# 3xA4B_rev2.net
KiCad netlist of a schematic drawn in EAGLE
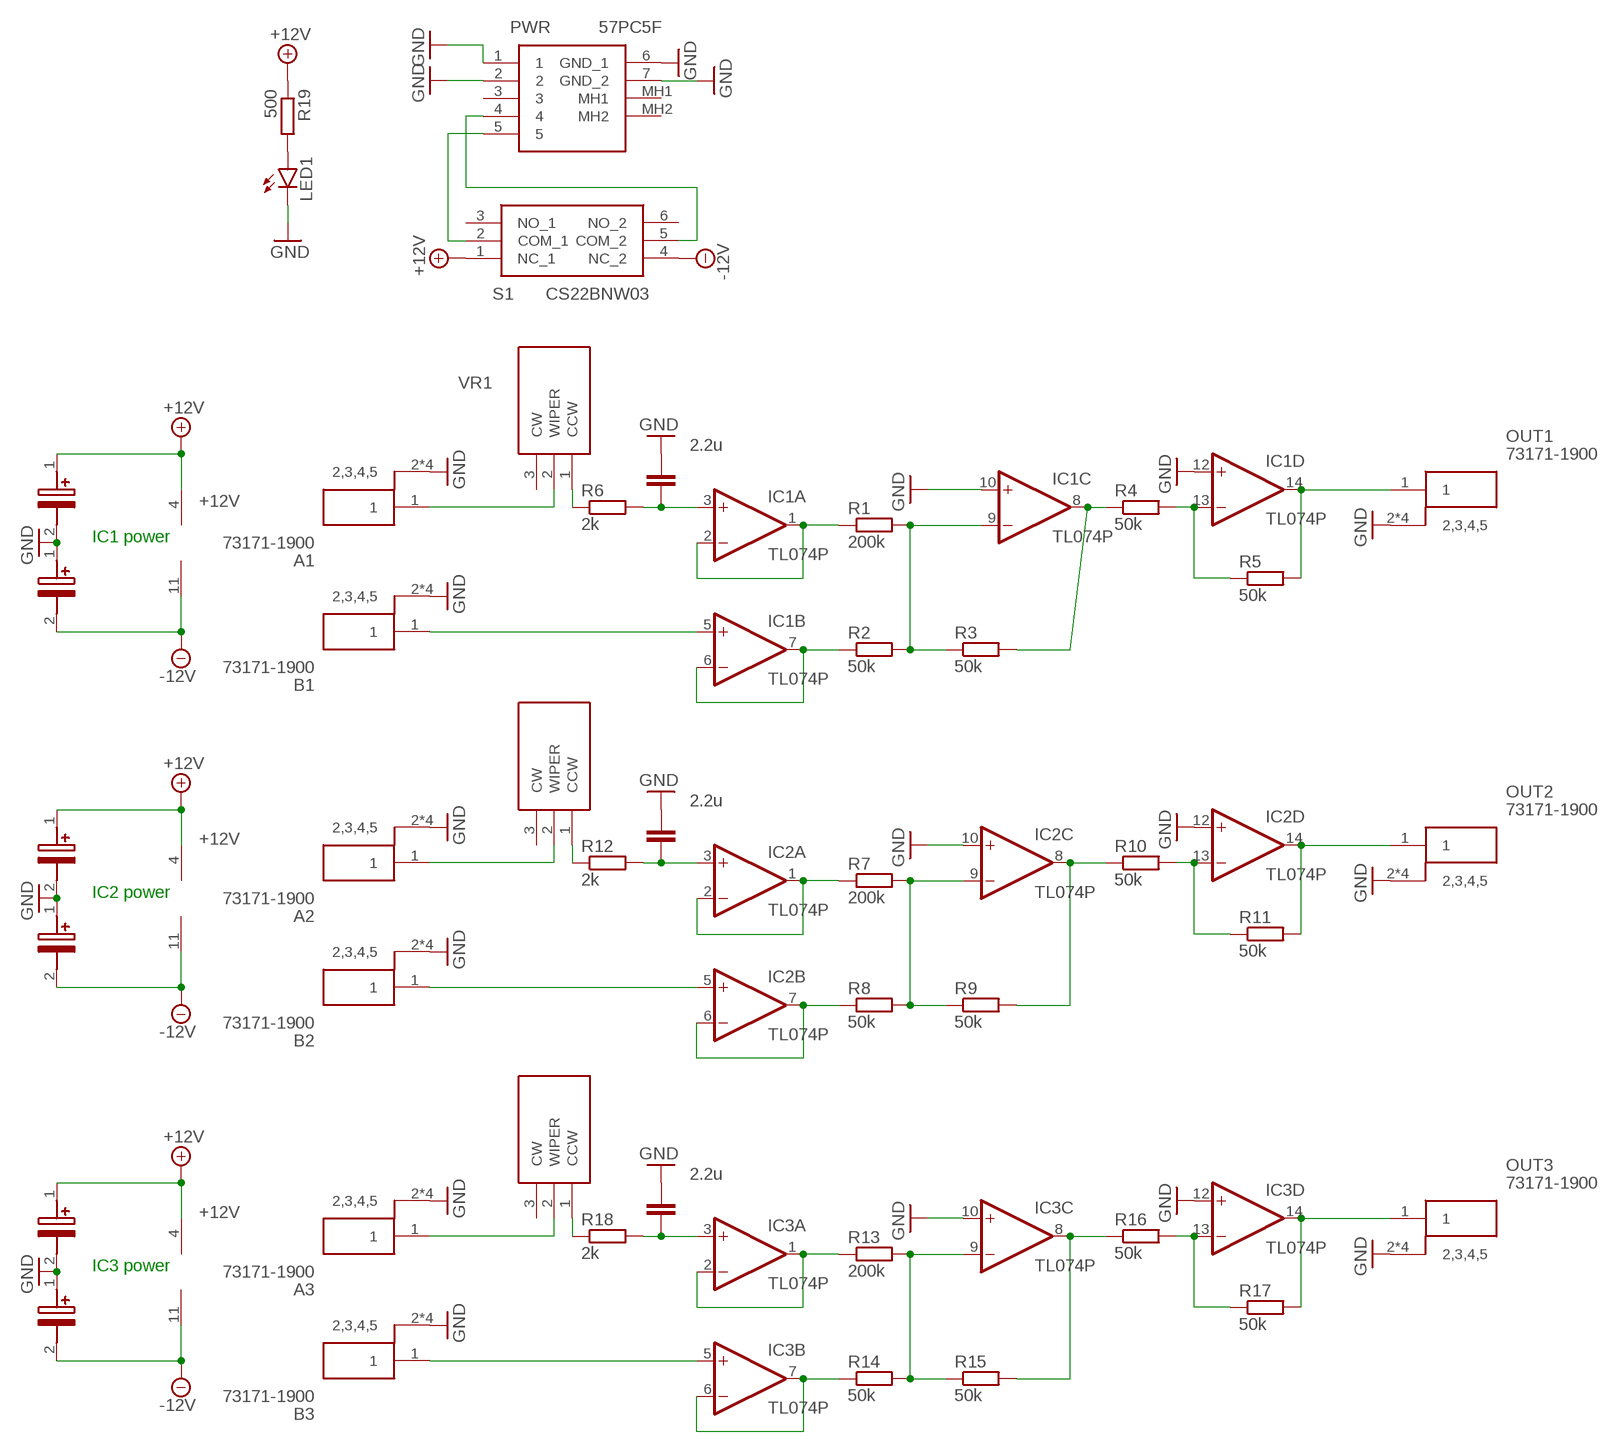
[diagram p0: schematic, sheet 1]

(export (version "E")
  (design (tool "Eeschema 10.0.6"))
  (components
    (comp (ref "A1")
      (value "73171-1900")
      (footprint "eagle-import:73171-1900")
      (fields (field (name "MOUSER_PART_NUMBER") "538-73171-1900"))
      (libsource (lib "eagle-import") (part "73171-1900"))
    )
    (comp (ref "A2")
      (value "73171-1900")
      (footprint "eagle-import:73171-1900")
      (fields (field (name "MOUSER_PART_NUMBER") "538-73171-1900"))
      (libsource (lib "eagle-import") (part "73171-1900"))
    )
    (comp (ref "A3")
      (value "73171-1900")
      (footprint "eagle-import:73171-1900")
      (fields (field (name "MOUSER_PART_NUMBER") "538-73171-1900"))
      (libsource (lib "eagle-import") (part "73171-1900"))
    )
    (comp (ref "B1")
      (value "73171-1900")
      (footprint "eagle-import:73171-1900")
      (fields (field (name "MOUSER_PART_NUMBER") "538-73171-1900"))
      (libsource (lib "eagle-import") (part "73171-1900"))
    )
    (comp (ref "B2")
      (value "73171-1900")
      (footprint "eagle-import:73171-1900")
      (fields (field (name "MOUSER_PART_NUMBER") "538-73171-1900"))
      (libsource (lib "eagle-import") (part "73171-1900"))
    )
    (comp (ref "B3")
      (value "73171-1900")
      (footprint "eagle-import:73171-1900")
      (fields (field (name "MOUSER_PART_NUMBER") "538-73171-1900"))
      (libsource (lib "eagle-import") (part "73171-1900"))
    )
    (comp (ref "C1")
      (value "TAP225K050GSB")
      (footprint "eagle-import:TAP225K050GSB")
      (fields (field (name "MOUSER_PART_NUMBER") "581-TAP225K050GSB"))
      (libsource (lib "eagle-import") (part "TAP225K050GSB"))
    )
    (comp (ref "C2")
      (value "TAP225K050GSB")
      (footprint "eagle-import:TAP225K050GSB")
      (fields (field (name "MOUSER_PART_NUMBER") "581-TAP225K050GSB"))
      (libsource (lib "eagle-import") (part "TAP225K050GSB"))
    )
    (comp (ref "C3")
      (value "TAP225K050GSB")
      (footprint "eagle-import:TAP225K050GSB")
      (fields (field (name "MOUSER_PART_NUMBER") "581-TAP225K050GSB"))
      (libsource (lib "eagle-import") (part "TAP225K050GSB"))
    )
    (comp (ref "C4")
      (value "TAP225K050GSB")
      (footprint "eagle-import:TAP225K050GSB")
      (fields (field (name "MOUSER_PART_NUMBER") "581-TAP225K050GSB"))
      (libsource (lib "eagle-import") (part "TAP225K050GSB"))
    )
    (comp (ref "C5")
      (value "TAP225K050GSB")
      (footprint "eagle-import:TAP225K050GSB")
      (fields (field (name "MOUSER_PART_NUMBER") "581-TAP225K050GSB"))
      (libsource (lib "eagle-import") (part "TAP225K050GSB"))
    )
    (comp (ref "C6")
      (value "TAP225K050GSB")
      (footprint "eagle-import:TAP225K050GSB")
      (fields (field (name "MOUSER_PART_NUMBER") "581-TAP225K050GSB"))
      (libsource (lib "eagle-import") (part "TAP225K050GSB"))
    )
    (comp (ref "IC1")
      (value "TL074P")
      (footprint "eagle-import:DIL14")
      (fields (field (name "OC_NEWARK") "unknown"))
      (libsource (lib "eagle-import") (part "TL074P"))
    )
    (comp (ref "IC2")
      (value "TL074P")
      (footprint "eagle-import:DIL14")
      (fields (field (name "OC_NEWARK") "unknown"))
      (libsource (lib "eagle-import") (part "TL074P"))
    )
    (comp (ref "IC3")
      (value "TL074P")
      (footprint "eagle-import:DIL14")
      (fields (field (name "OC_NEWARK") "unknown"))
      (libsource (lib "eagle-import") (part "TL074P"))
    )
    (comp (ref "LED1")
      (value "LED3MM")
      (footprint "eagle-import:LED3MM")
      (libsource (lib "eagle-import") (part "LED3MM"))
    )
    (comp (ref "OUT1")
      (value "73171-1900")
      (footprint "eagle-import:73171-1900")
      (fields (field (name "MOUSER_PART_NUMBER") "538-73171-1900"))
      (libsource (lib "eagle-import") (part "73171-1900"))
    )
    (comp (ref "OUT2")
      (value "73171-1900")
      (footprint "eagle-import:73171-1900")
      (fields (field (name "MOUSER_PART_NUMBER") "538-73171-1900"))
      (libsource (lib "eagle-import") (part "73171-1900"))
    )
    (comp (ref "OUT3")
      (value "73171-1900")
      (footprint "eagle-import:73171-1900")
      (fields (field (name "MOUSER_PART_NUMBER") "538-73171-1900"))
      (libsource (lib "eagle-import") (part "73171-1900"))
    )
    (comp (ref "PWR")
      (value "57PC5F")
      (footprint "eagle-import:57PC5F")
      (fields (field (name "MOUSER_PART_NUMBER") "502-57PC5F") (field (name "MF") "SWITCHCRAFT/CONXALL"))
      (libsource (lib "eagle-import") (part "57PC5F"))
    )
    (comp (ref "R1")
      (value "200k")
      (footprint "eagle-import:0207_10")
      (libsource (lib "eagle-import") (part "R-EU_0207/10"))
    )
    (comp (ref "R2")
      (value "50k")
      (footprint "eagle-import:0207_10")
      (libsource (lib "eagle-import") (part "R-EU_0207/10"))
    )
    (comp (ref "R3")
      (value "50k")
      (footprint "eagle-import:0207_10")
      (libsource (lib "eagle-import") (part "R-EU_0207/10"))
    )
    (comp (ref "R4")
      (value "50k")
      (footprint "eagle-import:0207_10")
      (libsource (lib "eagle-import") (part "R-EU_0207/10"))
    )
    (comp (ref "R5")
      (value "50k")
      (footprint "eagle-import:0207_10")
      (libsource (lib "eagle-import") (part "R-EU_0207/10"))
    )
    (comp (ref "R6")
      (value "2k")
      (footprint "eagle-import:0207_10")
      (libsource (lib "eagle-import") (part "R-EU_0207/10"))
    )
    (comp (ref "R7")
      (value "200k")
      (footprint "eagle-import:0207_10")
      (libsource (lib "eagle-import") (part "R-EU_0207/10"))
    )
    (comp (ref "R8")
      (value "50k")
      (footprint "eagle-import:0207_10")
      (libsource (lib "eagle-import") (part "R-EU_0207/10"))
    )
    (comp (ref "R9")
      (value "50k")
      (footprint "eagle-import:0207_10")
      (libsource (lib "eagle-import") (part "R-EU_0207/10"))
    )
    (comp (ref "R10")
      (value "50k")
      (footprint "eagle-import:0207_10")
      (libsource (lib "eagle-import") (part "R-EU_0207/10"))
    )
    (comp (ref "R11")
      (value "50k")
      (footprint "eagle-import:0207_10")
      (libsource (lib "eagle-import") (part "R-EU_0207/10"))
    )
    (comp (ref "R12")
      (value "2k")
      (footprint "eagle-import:0207_10")
      (libsource (lib "eagle-import") (part "R-EU_0207/10"))
    )
    (comp (ref "R13")
      (value "200k")
      (footprint "eagle-import:0207_10")
      (libsource (lib "eagle-import") (part "R-EU_0207/10"))
    )
    (comp (ref "R14")
      (value "50k")
      (footprint "eagle-import:0207_10")
      (libsource (lib "eagle-import") (part "R-EU_0207/10"))
    )
    (comp (ref "R15")
      (value "50k")
      (footprint "eagle-import:0207_10")
      (libsource (lib "eagle-import") (part "R-EU_0207/10"))
    )
    (comp (ref "R16")
      (value "50k")
      (footprint "eagle-import:0207_10")
      (libsource (lib "eagle-import") (part "R-EU_0207/10"))
    )
    (comp (ref "R17")
      (value "50k")
      (footprint "eagle-import:0207_10")
      (libsource (lib "eagle-import") (part "R-EU_0207/10"))
    )
    (comp (ref "R18")
      (value "2k")
      (footprint "eagle-import:0207_10")
      (libsource (lib "eagle-import") (part "R-EU_0207/10"))
    )
    (comp (ref "R19")
      (value "500")
      (footprint "eagle-import:0207_10")
      (libsource (lib "eagle-import") (part "R-EU_0207/10"))
    )
    (comp (ref "S1")
      (value "CS22BNW03")
      (footprint "eagle-import:CS22BNW03")
      (fields (field (name "MOUSER_PART_NUMBER") "633-CS22BNW03") (field (name "MF") "NKK SWITCHES"))
      (libsource (lib "eagle-import") (part "CS22BNW03"))
    )
    (comp (ref "VC1")
      (value "2.2u")
      (footprint "eagle-import:C025-024X044")
      (libsource (lib "eagle-import") (part "C-EU025-024X044"))
    )
    (comp (ref "VC2")
      (value "2.2u")
      (footprint "eagle-import:C025-024X044")
      (libsource (lib "eagle-import") (part "C-EU025-024X044"))
    )
    (comp (ref "VC3")
      (value "2.2u")
      (footprint "eagle-import:C025-024X044")
      (libsource (lib "eagle-import") (part "C-EU025-024X044"))
    )
    (comp (ref "VR1")
      (value "3299W-1-104LF")
      (footprint "eagle-import:3299W-1-104LF_1")
      (fields (field (name "MOUSER_PART_NUMBER") "652-3299W-1-104LF") (field (name "MF") "BOURNS"))
      (libsource (lib "eagle-import") (part "3299W-1-104LF"))
    )
    (comp (ref "VR2")
      (value "3299W-1-104LF")
      (footprint "eagle-import:3299W-1-104LF_1")
      (fields (field (name "MOUSER_PART_NUMBER") "652-3299W-1-104LF") (field (name "MF") "BOURNS"))
      (libsource (lib "eagle-import") (part "3299W-1-104LF"))
    )
    (comp (ref "VR3")
      (value "3299W-1-104LF")
      (footprint "eagle-import:3299W-1-104LF_1")
      (fields (field (name "MOUSER_PART_NUMBER") "652-3299W-1-104LF") (field (name "MF") "BOURNS"))
      (libsource (lib "eagle-import") (part "3299W-1-104LF"))
    )
  )
  (nets
    (net (code "1") (name "+12V") (class "Default")
      (node (ref "C1") (pin "1") (pinfunction "+_1") (pintype "bidirectional"))
      (node (ref "C3") (pin "1") (pinfunction "+_1") (pintype "bidirectional"))
      (node (ref "C5") (pin "1") (pinfunction "+_1") (pintype "bidirectional"))
      (node (ref "IC1") (pin "4") (pinfunction "V+_4") (pintype "power_in"))
      (node (ref "IC2") (pin "4") (pinfunction "V+_4") (pintype "power_in"))
      (node (ref "IC3") (pin "4") (pinfunction "V+_4") (pintype "power_in"))
      (node (ref "R19") (pin "1") (pinfunction "1_1") (pintype "passive"))
      (node (ref "S1") (pin "1") (pinfunction "NC_1_1") (pintype "bidirectional"))
    )
    (net (code "2") (name "-12V") (class "Default")
      (node (ref "C2") (pin "2") (pinfunction "-_2") (pintype "bidirectional"))
      (node (ref "C4") (pin "2") (pinfunction "-_2") (pintype "bidirectional"))
      (node (ref "C6") (pin "2") (pinfunction "-_2") (pintype "bidirectional"))
      (node (ref "IC1") (pin "11") (pinfunction "V-_11") (pintype "power_in"))
      (node (ref "IC2") (pin "11") (pinfunction "V-_11") (pintype "power_in"))
      (node (ref "IC3") (pin "11") (pinfunction "V-_11") (pintype "power_in"))
      (node (ref "S1") (pin "4") (pinfunction "NC_2_4") (pintype "bidirectional"))
    )
    (net (code "3") (name "GND") (class "Default")
      (node (ref "A1") (pin "2") (pinfunction "2,3,4,5_2") (pintype "bidirectional"))
      (node (ref "A1") (pin "3") (pinfunction "2,3,4,5_3") (pintype "bidirectional"))
      (node (ref "A1") (pin "4") (pinfunction "2,3,4,5_4") (pintype "bidirectional"))
      (node (ref "A1") (pin "5") (pinfunction "2,3,4,5_5") (pintype "bidirectional"))
      (node (ref "A2") (pin "2") (pinfunction "2,3,4,5_2") (pintype "bidirectional"))
      (node (ref "A2") (pin "3") (pinfunction "2,3,4,5_3") (pintype "bidirectional"))
      (node (ref "A2") (pin "4") (pinfunction "2,3,4,5_4") (pintype "bidirectional"))
      (node (ref "A2") (pin "5") (pinfunction "2,3,4,5_5") (pintype "bidirectional"))
      (node (ref "A3") (pin "2") (pinfunction "2,3,4,5_2") (pintype "bidirectional"))
      (node (ref "A3") (pin "3") (pinfunction "2,3,4,5_3") (pintype "bidirectional"))
      (node (ref "A3") (pin "4") (pinfunction "2,3,4,5_4") (pintype "bidirectional"))
      (node (ref "A3") (pin "5") (pinfunction "2,3,4,5_5") (pintype "bidirectional"))
      (node (ref "B1") (pin "2") (pinfunction "2,3,4,5_2") (pintype "bidirectional"))
      (node (ref "B1") (pin "3") (pinfunction "2,3,4,5_3") (pintype "bidirectional"))
      (node (ref "B1") (pin "4") (pinfunction "2,3,4,5_4") (pintype "bidirectional"))
      (node (ref "B1") (pin "5") (pinfunction "2,3,4,5_5") (pintype "bidirectional"))
      (node (ref "B2") (pin "2") (pinfunction "2,3,4,5_2") (pintype "bidirectional"))
      (node (ref "B2") (pin "3") (pinfunction "2,3,4,5_3") (pintype "bidirectional"))
      (node (ref "B2") (pin "4") (pinfunction "2,3,4,5_4") (pintype "bidirectional"))
      (node (ref "B2") (pin "5") (pinfunction "2,3,4,5_5") (pintype "bidirectional"))
      (node (ref "B3") (pin "2") (pinfunction "2,3,4,5_2") (pintype "bidirectional"))
      (node (ref "B3") (pin "3") (pinfunction "2,3,4,5_3") (pintype "bidirectional"))
      (node (ref "B3") (pin "4") (pinfunction "2,3,4,5_4") (pintype "bidirectional"))
      (node (ref "B3") (pin "5") (pinfunction "2,3,4,5_5") (pintype "bidirectional"))
      (node (ref "C1") (pin "2") (pinfunction "-_2") (pintype "bidirectional"))
      (node (ref "C2") (pin "1") (pinfunction "+_1") (pintype "bidirectional"))
      (node (ref "C3") (pin "2") (pinfunction "-_2") (pintype "bidirectional"))
      (node (ref "C4") (pin "1") (pinfunction "+_1") (pintype "bidirectional"))
      (node (ref "C5") (pin "2") (pinfunction "-_2") (pintype "bidirectional"))
      (node (ref "C6") (pin "1") (pinfunction "+_1") (pintype "bidirectional"))
      (node (ref "IC1") (pin "10") (pinfunction "+IN_10") (pintype "input"))
      (node (ref "IC1") (pin "12") (pinfunction "+IN_12") (pintype "input"))
      (node (ref "IC2") (pin "10") (pinfunction "+IN_10") (pintype "input"))
      (node (ref "IC2") (pin "12") (pinfunction "+IN_12") (pintype "input"))
      (node (ref "IC3") (pin "10") (pinfunction "+IN_10") (pintype "input"))
      (node (ref "IC3") (pin "12") (pinfunction "+IN_12") (pintype "input"))
      (node (ref "LED1") (pin "K") (pinfunction "C_K") (pintype "passive"))
      (node (ref "OUT1") (pin "2") (pinfunction "2,3,4,5_2") (pintype "bidirectional"))
      (node (ref "OUT1") (pin "3") (pinfunction "2,3,4,5_3") (pintype "bidirectional"))
      (node (ref "OUT1") (pin "4") (pinfunction "2,3,4,5_4") (pintype "bidirectional"))
      (node (ref "OUT1") (pin "5") (pinfunction "2,3,4,5_5") (pintype "bidirectional"))
      (node (ref "OUT2") (pin "2") (pinfunction "2,3,4,5_2") (pintype "bidirectional"))
      (node (ref "OUT2") (pin "3") (pinfunction "2,3,4,5_3") (pintype "bidirectional"))
      (node (ref "OUT2") (pin "4") (pinfunction "2,3,4,5_4") (pintype "bidirectional"))
      (node (ref "OUT2") (pin "5") (pinfunction "2,3,4,5_5") (pintype "bidirectional"))
      (node (ref "OUT3") (pin "2") (pinfunction "2,3,4,5_2") (pintype "bidirectional"))
      (node (ref "OUT3") (pin "3") (pinfunction "2,3,4,5_3") (pintype "bidirectional"))
      (node (ref "OUT3") (pin "4") (pinfunction "2,3,4,5_4") (pintype "bidirectional"))
      (node (ref "OUT3") (pin "5") (pinfunction "2,3,4,5_5") (pintype "bidirectional"))
      (node (ref "PWR") (pin "1") (pinfunction "1_1") (pintype "bidirectional"))
      (node (ref "PWR") (pin "2") (pinfunction "2_2") (pintype "bidirectional"))
      (node (ref "PWR") (pin "6") (pinfunction "GND_1_6") (pintype "bidirectional"))
      (node (ref "PWR") (pin "7") (pinfunction "GND_2_7") (pintype "bidirectional"))
      (node (ref "VC1") (pin "1") (pinfunction "1_1") (pintype "passive"))
      (node (ref "VC2") (pin "1") (pinfunction "1_1") (pintype "passive"))
      (node (ref "VC3") (pin "1") (pinfunction "1_1") (pintype "passive"))
    )
    (net (code "4") (name "Net-(IC1A-+IN)") (class "Default")
      (node (ref "IC1") (pin "3") (pinfunction "+IN_3") (pintype "input"))
      (node (ref "R6") (pin "2") (pinfunction "2_2") (pintype "passive"))
      (node (ref "VC1") (pin "2") (pinfunction "2_2") (pintype "passive"))
    )
    (net (code "5") (name "Net-(IC1A--IN)") (class "Default")
      (node (ref "IC1") (pin "1") (pinfunction "OUT_1") (pintype "output"))
      (node (ref "IC1") (pin "2") (pinfunction "-IN_2") (pintype "input"))
      (node (ref "R1") (pin "1") (pinfunction "1_1") (pintype "passive"))
    )
    (net (code "6") (name "Net-(IC1B-+IN)") (class "Default")
      (node (ref "B1") (pin "1") (pinfunction "1_1") (pintype "bidirectional"))
      (node (ref "IC1") (pin "5") (pinfunction "+IN_5") (pintype "input"))
    )
    (net (code "7") (name "Net-(IC1B--IN)") (class "Default")
      (node (ref "IC1") (pin "6") (pinfunction "-IN_6") (pintype "input"))
      (node (ref "IC1") (pin "7") (pinfunction "OUT_7") (pintype "output"))
      (node (ref "R2") (pin "1") (pinfunction "1_1") (pintype "passive"))
    )
    (net (code "8") (name "Net-(IC1C--IN)") (class "Default")
      (node (ref "IC1") (pin "9") (pinfunction "-IN_9") (pintype "input"))
      (node (ref "R1") (pin "2") (pinfunction "2_2") (pintype "passive"))
      (node (ref "R2") (pin "2") (pinfunction "2_2") (pintype "passive"))
      (node (ref "R3") (pin "1") (pinfunction "1_1") (pintype "passive"))
    )
    (net (code "9") (name "Net-(IC1C-OUT)") (class "Default")
      (node (ref "IC1") (pin "8") (pinfunction "OUT_8") (pintype "output"))
      (node (ref "R3") (pin "2") (pinfunction "2_2") (pintype "passive"))
      (node (ref "R4") (pin "1") (pinfunction "1_1") (pintype "passive"))
    )
    (net (code "10") (name "Net-(IC1D--IN)") (class "Default")
      (node (ref "IC1") (pin "13") (pinfunction "-IN_13") (pintype "input"))
      (node (ref "R4") (pin "2") (pinfunction "2_2") (pintype "passive"))
      (node (ref "R5") (pin "1") (pinfunction "1_1") (pintype "passive"))
    )
    (net (code "11") (name "Net-(IC1D-OUT)") (class "Default")
      (node (ref "IC1") (pin "14") (pinfunction "OUT_14") (pintype "output"))
      (node (ref "OUT1") (pin "1") (pinfunction "1_1") (pintype "bidirectional"))
      (node (ref "R5") (pin "2") (pinfunction "2_2") (pintype "passive"))
    )
    (net (code "12") (name "Net-(IC2A-+IN)") (class "Default")
      (node (ref "IC2") (pin "3") (pinfunction "+IN_3") (pintype "input"))
      (node (ref "R12") (pin "2") (pinfunction "2_2") (pintype "passive"))
      (node (ref "VC2") (pin "2") (pinfunction "2_2") (pintype "passive"))
    )
    (net (code "13") (name "Net-(IC2A--IN)") (class "Default")
      (node (ref "IC2") (pin "1") (pinfunction "OUT_1") (pintype "output"))
      (node (ref "IC2") (pin "2") (pinfunction "-IN_2") (pintype "input"))
      (node (ref "R7") (pin "1") (pinfunction "1_1") (pintype "passive"))
    )
    (net (code "14") (name "Net-(IC2B-+IN)") (class "Default")
      (node (ref "B2") (pin "1") (pinfunction "1_1") (pintype "bidirectional"))
      (node (ref "IC2") (pin "5") (pinfunction "+IN_5") (pintype "input"))
    )
    (net (code "15") (name "Net-(IC2B--IN)") (class "Default")
      (node (ref "IC2") (pin "6") (pinfunction "-IN_6") (pintype "input"))
      (node (ref "IC2") (pin "7") (pinfunction "OUT_7") (pintype "output"))
      (node (ref "R8") (pin "1") (pinfunction "1_1") (pintype "passive"))
    )
    (net (code "16") (name "Net-(IC2C--IN)") (class "Default")
      (node (ref "IC2") (pin "9") (pinfunction "-IN_9") (pintype "input"))
      (node (ref "R7") (pin "2") (pinfunction "2_2") (pintype "passive"))
      (node (ref "R8") (pin "2") (pinfunction "2_2") (pintype "passive"))
      (node (ref "R9") (pin "1") (pinfunction "1_1") (pintype "passive"))
    )
    (net (code "17") (name "Net-(IC2C-OUT)") (class "Default")
      (node (ref "IC2") (pin "8") (pinfunction "OUT_8") (pintype "output"))
      (node (ref "R10") (pin "1") (pinfunction "1_1") (pintype "passive"))
      (node (ref "R9") (pin "2") (pinfunction "2_2") (pintype "passive"))
    )
    (net (code "18") (name "Net-(IC2D--IN)") (class "Default")
      (node (ref "IC2") (pin "13") (pinfunction "-IN_13") (pintype "input"))
      (node (ref "R10") (pin "2") (pinfunction "2_2") (pintype "passive"))
      (node (ref "R11") (pin "1") (pinfunction "1_1") (pintype "passive"))
    )
    (net (code "19") (name "Net-(IC2D-OUT)") (class "Default")
      (node (ref "IC2") (pin "14") (pinfunction "OUT_14") (pintype "output"))
      (node (ref "OUT2") (pin "1") (pinfunction "1_1") (pintype "bidirectional"))
      (node (ref "R11") (pin "2") (pinfunction "2_2") (pintype "passive"))
    )
    (net (code "20") (name "Net-(IC3A-+IN)") (class "Default")
      (node (ref "IC3") (pin "3") (pinfunction "+IN_3") (pintype "input"))
      (node (ref "R18") (pin "2") (pinfunction "2_2") (pintype "passive"))
      (node (ref "VC3") (pin "2") (pinfunction "2_2") (pintype "passive"))
    )
    (net (code "21") (name "Net-(IC3A--IN)") (class "Default")
      (node (ref "IC3") (pin "1") (pinfunction "OUT_1") (pintype "output"))
      (node (ref "IC3") (pin "2") (pinfunction "-IN_2") (pintype "input"))
      (node (ref "R13") (pin "1") (pinfunction "1_1") (pintype "passive"))
    )
    (net (code "22") (name "Net-(IC3B-+IN)") (class "Default")
      (node (ref "B3") (pin "1") (pinfunction "1_1") (pintype "bidirectional"))
      (node (ref "IC3") (pin "5") (pinfunction "+IN_5") (pintype "input"))
    )
    (net (code "23") (name "Net-(IC3B--IN)") (class "Default")
      (node (ref "IC3") (pin "6") (pinfunction "-IN_6") (pintype "input"))
      (node (ref "IC3") (pin "7") (pinfunction "OUT_7") (pintype "output"))
      (node (ref "R14") (pin "1") (pinfunction "1_1") (pintype "passive"))
    )
    (net (code "24") (name "Net-(IC3C--IN)") (class "Default")
      (node (ref "IC3") (pin "9") (pinfunction "-IN_9") (pintype "input"))
      (node (ref "R13") (pin "2") (pinfunction "2_2") (pintype "passive"))
      (node (ref "R14") (pin "2") (pinfunction "2_2") (pintype "passive"))
      (node (ref "R15") (pin "1") (pinfunction "1_1") (pintype "passive"))
    )
    (net (code "25") (name "Net-(IC3C-OUT)") (class "Default")
      (node (ref "IC3") (pin "8") (pinfunction "OUT_8") (pintype "output"))
      (node (ref "R15") (pin "2") (pinfunction "2_2") (pintype "passive"))
      (node (ref "R16") (pin "1") (pinfunction "1_1") (pintype "passive"))
    )
    (net (code "26") (name "Net-(IC3D--IN)") (class "Default")
      (node (ref "IC3") (pin "13") (pinfunction "-IN_13") (pintype "input"))
      (node (ref "R16") (pin "2") (pinfunction "2_2") (pintype "passive"))
      (node (ref "R17") (pin "1") (pinfunction "1_1") (pintype "passive"))
    )
    (net (code "27") (name "Net-(IC3D-OUT)") (class "Default")
      (node (ref "IC3") (pin "14") (pinfunction "OUT_14") (pintype "output"))
      (node (ref "OUT3") (pin "1") (pinfunction "1_1") (pintype "bidirectional"))
      (node (ref "R17") (pin "2") (pinfunction "2_2") (pintype "passive"))
    )
    (net (code "28") (name "Net-(LED1-PadA)") (class "Default")
      (node (ref "LED1") (pin "A") (pinfunction "A_A") (pintype "passive"))
      (node (ref "R19") (pin "2") (pinfunction "2_2") (pintype "passive"))
    )
    (net (code "29") (name "Net-(S1-COM_1)") (class "Default")
      (node (ref "PWR") (pin "5") (pinfunction "5_5") (pintype "bidirectional"))
      (node (ref "S1") (pin "2") (pinfunction "COM_1_2") (pintype "bidirectional"))
    )
    (net (code "30") (name "Net-(S1-COM_2)") (class "Default")
      (node (ref "PWR") (pin "4") (pinfunction "4_4") (pintype "bidirectional"))
      (node (ref "S1") (pin "5") (pinfunction "COM_2_5") (pintype "bidirectional"))
    )
    (net (code "31") (name "Net-(VR1-CCW)") (class "Default")
      (node (ref "R6") (pin "1") (pinfunction "1_1") (pintype "passive"))
      (node (ref "VR1") (pin "1") (pinfunction "CCW_1") (pintype "bidirectional"))
    )
    (net (code "32") (name "Net-(VR1-WIPER)") (class "Default")
      (node (ref "A1") (pin "1") (pinfunction "1_1") (pintype "bidirectional"))
      (node (ref "VR1") (pin "2") (pinfunction "WIPER_2") (pintype "bidirectional"))
    )
    (net (code "33") (name "Net-(VR2-CCW)") (class "Default")
      (node (ref "R12") (pin "1") (pinfunction "1_1") (pintype "passive"))
      (node (ref "VR2") (pin "1") (pinfunction "CCW_1") (pintype "bidirectional"))
    )
    (net (code "34") (name "Net-(VR2-WIPER)") (class "Default")
      (node (ref "A2") (pin "1") (pinfunction "1_1") (pintype "bidirectional"))
      (node (ref "VR2") (pin "2") (pinfunction "WIPER_2") (pintype "bidirectional"))
    )
    (net (code "35") (name "Net-(VR3-CCW)") (class "Default")
      (node (ref "R18") (pin "1") (pinfunction "1_1") (pintype "passive"))
      (node (ref "VR3") (pin "1") (pinfunction "CCW_1") (pintype "bidirectional"))
    )
    (net (code "36") (name "Net-(VR3-WIPER)") (class "Default")
      (node (ref "A3") (pin "1") (pinfunction "1_1") (pintype "bidirectional"))
      (node (ref "VR3") (pin "2") (pinfunction "WIPER_2") (pintype "bidirectional"))
    )
    (net (code "37") (name "unconnected-(PWR-Pad3)") (class "Default")
      (node (ref "PWR") (pin "3") (pinfunction "3_3") (pintype "bidirectional"))
    )
    (net (code "38") (name "unconnected-(PWR-PadMH1)") (class "Default")
      (node (ref "PWR") (pin "MH1") (pinfunction "MH1_MH1") (pintype "bidirectional"))
    )
    (net (code "39") (name "unconnected-(PWR-PadMH2)") (class "Default")
      (node (ref "PWR") (pin "MH2") (pinfunction "MH2_MH2") (pintype "bidirectional"))
    )
    (net (code "40") (name "unconnected-(S1-NO_1-Pad3)") (class "Default")
      (node (ref "S1") (pin "3") (pinfunction "NO_1_3") (pintype "bidirectional"))
    )
    (net (code "41") (name "unconnected-(S1-NO_2-Pad6)") (class "Default")
      (node (ref "S1") (pin "6") (pinfunction "NO_2_6") (pintype "bidirectional"))
    )
    (net (code "42") (name "unconnected-(VR1-CW-Pad3)") (class "Default")
      (node (ref "VR1") (pin "3") (pinfunction "CW_3") (pintype "bidirectional"))
    )
    (net (code "43") (name "unconnected-(VR2-CW-Pad3)") (class "Default")
      (node (ref "VR2") (pin "3") (pinfunction "CW_3") (pintype "bidirectional"))
    )
    (net (code "44") (name "unconnected-(VR3-CW-Pad3)") (class "Default")
      (node (ref "VR3") (pin "3") (pinfunction "CW_3") (pintype "bidirectional"))
    )
  )
)
